# Mega_Shield-v13.net
KiCad netlist of a schematic drawn in EAGLE
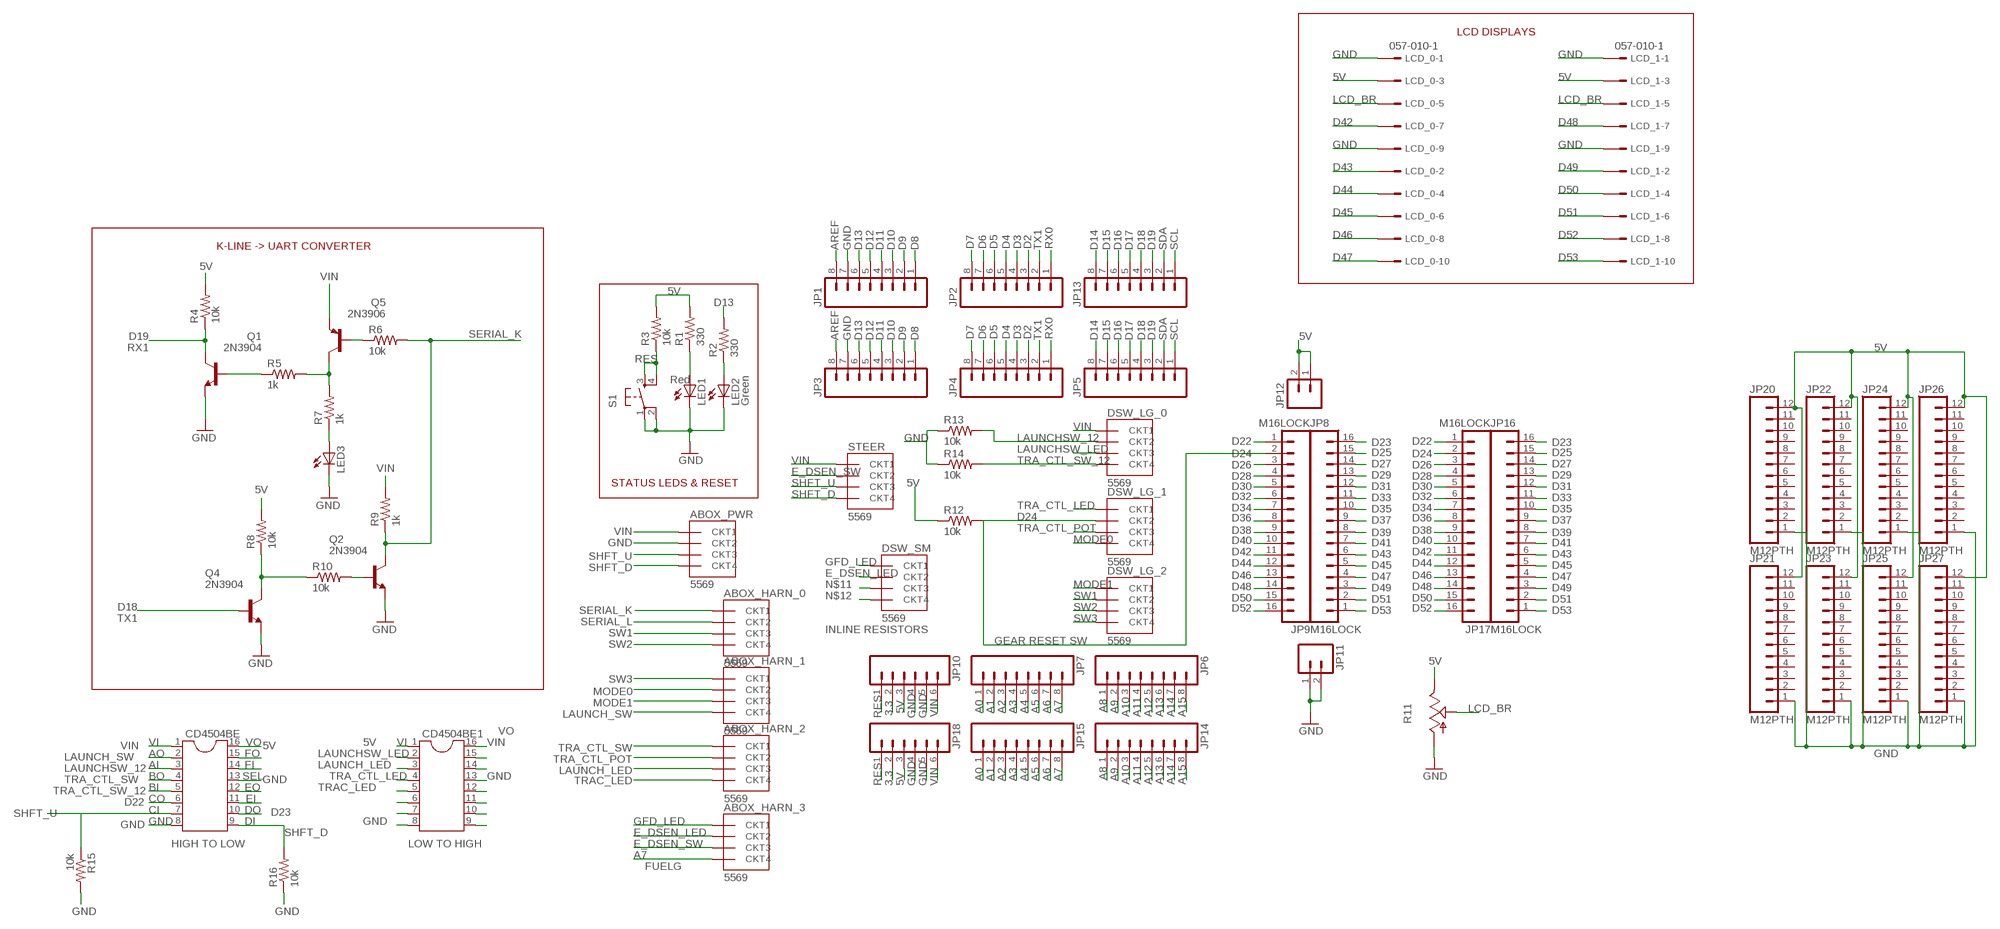
[diagram p0: schematic, sheet 1]

(export (version "E")
  (design (tool "Eeschema 10.0.6"))
  (components
    (comp (ref "ABOX_HARN_0")
      (value "5569")
      (footprint "eagle-import:5569")
      (libsource (lib "eagle-import") (part "5569"))
    )
    (comp (ref "ABOX_HARN_1")
      (value "5569")
      (footprint "eagle-import:5569")
      (libsource (lib "eagle-import") (part "5569"))
    )
    (comp (ref "ABOX_HARN_2")
      (value "5569")
      (footprint "eagle-import:5569")
      (libsource (lib "eagle-import") (part "5569"))
    )
    (comp (ref "ABOX_HARN_3")
      (value "5569")
      (footprint "eagle-import:5569")
      (libsource (lib "eagle-import") (part "5569"))
    )
    (comp (ref "ABOX_PWR")
      (value "5569")
      (footprint "eagle-import:5569")
      (libsource (lib "eagle-import") (part "5569"))
    )
    (comp (ref "CD4504BE")
      (value "DIL16S")
      (footprint "eagle-import:SOCKET-16")
      (libsource (lib "eagle-import") (part "DIL16S"))
    )
    (comp (ref "CD4504BE1")
      (value "DIL16S")
      (footprint "eagle-import:SOCKET-16")
      (libsource (lib "eagle-import") (part "DIL16S"))
    )
    (comp (ref "DSW_LG_0")
      (value "5569")
      (footprint "eagle-import:5569")
      (libsource (lib "eagle-import") (part "5569"))
    )
    (comp (ref "DSW_LG_1")
      (value "5569")
      (footprint "eagle-import:5569")
      (libsource (lib "eagle-import") (part "5569"))
    )
    (comp (ref "DSW_LG_2")
      (value "5569")
      (footprint "eagle-import:5569")
      (libsource (lib "eagle-import") (part "5569"))
    )
    (comp (ref "DSW_SM")
      (value "5569")
      (footprint "eagle-import:5569")
      (libsource (lib "eagle-import") (part "5569"))
    )
    (comp (ref "JP1")
      (value "M08LOCK")
      (footprint "eagle-import:1X08_LOCK")
      (libsource (lib "eagle-import") (part "M08LOCK"))
    )
    (comp (ref "JP2")
      (value "M08LOCK")
      (footprint "eagle-import:1X08_LOCK")
      (libsource (lib "eagle-import") (part "M08LOCK"))
    )
    (comp (ref "JP3")
      (value "M08LOCK")
      (footprint "eagle-import:1X08_LOCK")
      (libsource (lib "eagle-import") (part "M08LOCK"))
    )
    (comp (ref "JP4")
      (value "M08LOCK")
      (footprint "eagle-import:1X08_LOCK")
      (libsource (lib "eagle-import") (part "M08LOCK"))
    )
    (comp (ref "JP5")
      (value "M08LOCK")
      (footprint "eagle-import:1X08_LOCK")
      (libsource (lib "eagle-import") (part "M08LOCK"))
    )
    (comp (ref "JP6")
      (value "M08LOCK")
      (footprint "eagle-import:1X08_LOCK")
      (libsource (lib "eagle-import") (part "M08LOCK"))
    )
    (comp (ref "JP7")
      (value "M08LOCK")
      (footprint "eagle-import:1X08_LOCK")
      (libsource (lib "eagle-import") (part "M08LOCK"))
    )
    (comp (ref "JP8")
      (value "M16LOCK")
      (footprint "eagle-import:1X16_LOCK")
      (libsource (lib "eagle-import") (part "M16LOCK"))
    )
    (comp (ref "JP9")
      (value "M16LOCK")
      (footprint "eagle-import:1X16_LOCK")
      (libsource (lib "eagle-import") (part "M16LOCK"))
    )
    (comp (ref "JP10")
      (value "M06LOCK")
      (footprint "eagle-import:1X06_LOCK")
      (libsource (lib "eagle-import") (part "M06LOCK"))
    )
    (comp (ref "JP11")
      (value "M02LOCK")
      (footprint "eagle-import:1X02_LOCK")
      (libsource (lib "eagle-import") (part "M02LOCK"))
    )
    (comp (ref "JP12")
      (value "M02LOCK")
      (footprint "eagle-import:1X02_LOCK")
      (libsource (lib "eagle-import") (part "M02LOCK"))
    )
    (comp (ref "JP13")
      (value "M08LOCK")
      (footprint "eagle-import:1X08_LOCK")
      (libsource (lib "eagle-import") (part "M08LOCK"))
    )
    (comp (ref "JP14")
      (value "M08LOCK")
      (footprint "eagle-import:1X08_LOCK")
      (libsource (lib "eagle-import") (part "M08LOCK"))
    )
    (comp (ref "JP15")
      (value "M08LOCK")
      (footprint "eagle-import:1X08_LOCK")
      (libsource (lib "eagle-import") (part "M08LOCK"))
    )
    (comp (ref "JP16")
      (value "M16LOCK")
      (footprint "eagle-import:1X16_LOCK")
      (libsource (lib "eagle-import") (part "M16LOCK"))
    )
    (comp (ref "JP17")
      (value "M16LOCK")
      (footprint "eagle-import:1X16_LOCK")
      (libsource (lib "eagle-import") (part "M16LOCK"))
    )
    (comp (ref "JP18")
      (value "M06LOCK")
      (footprint "eagle-import:1X06_LOCK")
      (libsource (lib "eagle-import") (part "M06LOCK"))
    )
    (comp (ref "JP20")
      (value "M12PTH")
      (footprint "eagle-import:1X12")
      (libsource (lib "eagle-import") (part "M12PTH"))
    )
    (comp (ref "JP21")
      (value "M12PTH")
      (footprint "eagle-import:1X12")
      (libsource (lib "eagle-import") (part "M12PTH"))
    )
    (comp (ref "JP22")
      (value "M12PTH")
      (footprint "eagle-import:1X12")
      (libsource (lib "eagle-import") (part "M12PTH"))
    )
    (comp (ref "JP23")
      (value "M12PTH")
      (footprint "eagle-import:1X12")
      (libsource (lib "eagle-import") (part "M12PTH"))
    )
    (comp (ref "JP24")
      (value "M12PTH")
      (footprint "eagle-import:1X12")
      (libsource (lib "eagle-import") (part "M12PTH"))
    )
    (comp (ref "JP25")
      (value "M12PTH")
      (footprint "eagle-import:1X12")
      (libsource (lib "eagle-import") (part "M12PTH"))
    )
    (comp (ref "JP26")
      (value "M12PTH")
      (footprint "eagle-import:1X12")
      (libsource (lib "eagle-import") (part "M12PTH"))
    )
    (comp (ref "JP27")
      (value "M12PTH")
      (footprint "eagle-import:1X12")
      (libsource (lib "eagle-import") (part "M12PTH"))
    )
    (comp (ref "LCD_0")
      (value "057-010-1")
      (footprint "eagle-import:057-010-1")
      (libsource (lib "eagle-import") (part "057-010-1"))
    )
    (comp (ref "LCD_1")
      (value "057-010-1")
      (footprint "eagle-import:057-010-1")
      (libsource (lib "eagle-import") (part "057-010-1"))
    )
    (comp (ref "LED1")
      (value "Red")
      (footprint "eagle-import:LED5MM")
      (libsource (lib "eagle-import") (part "LED5MM"))
    )
    (comp (ref "LED2")
      (value "Green")
      (footprint "eagle-import:LED5MM")
      (libsource (lib "eagle-import") (part "LED5MM"))
    )
    (comp (ref "LED3")
      (value "LED5MM")
      (footprint "eagle-import:LED5MM")
      (libsource (lib "eagle-import") (part "led_LED5MM"))
    )
    (comp (ref "Q1")
      (value "2N3904")
      (footprint "eagle-import:TO92")
      (libsource (lib "eagle-import") (part "2N3904"))
    )
    (comp (ref "Q2")
      (value "2N3904")
      (footprint "eagle-import:TO92")
      (libsource (lib "eagle-import") (part "2N3904"))
    )
    (comp (ref "Q4")
      (value "2N3904")
      (footprint "eagle-import:TO92")
      (libsource (lib "eagle-import") (part "2N3904"))
    )
    (comp (ref "Q5")
      (value "2N3906")
      (footprint "eagle-import:TO92")
      (libsource (lib "eagle-import") (part "2N3906"))
    )
    (comp (ref "R1")
      (value "330")
      (footprint "eagle-import:AXIAL-0.3")
      (libsource (lib "eagle-import") (part "RESISTORPTH1"))
    )
    (comp (ref "R2")
      (value "330")
      (footprint "eagle-import:AXIAL-0.3")
      (libsource (lib "eagle-import") (part "RESISTORPTH1"))
    )
    (comp (ref "R3")
      (value "10k")
      (footprint "eagle-import:AXIAL-0.3")
      (libsource (lib "eagle-import") (part "RESISTORPTH1"))
    )
    (comp (ref "R4")
      (value "10k")
      (footprint "eagle-import:AXIAL-0.3EZ")
      (libsource (lib "eagle-import") (part "RESISTOREZ"))
    )
    (comp (ref "R5")
      (value "1k")
      (footprint "eagle-import:AXIAL-0.3EZ")
      (libsource (lib "eagle-import") (part "RESISTOREZ"))
    )
    (comp (ref "R6")
      (value "10k")
      (footprint "eagle-import:AXIAL-0.3EZ")
      (libsource (lib "eagle-import") (part "RESISTOREZ"))
    )
    (comp (ref "R7")
      (value "1k")
      (footprint "eagle-import:AXIAL-0.3EZ")
      (libsource (lib "eagle-import") (part "RESISTOREZ"))
    )
    (comp (ref "R8")
      (value "10k")
      (footprint "eagle-import:AXIAL-0.3EZ")
      (libsource (lib "eagle-import") (part "RESISTOREZ"))
    )
    (comp (ref "R9")
      (value "1k")
      (footprint "eagle-import:AXIAL-0.3EZ")
      (libsource (lib "eagle-import") (part "RESISTOREZ"))
    )
    (comp (ref "R10")
      (value "10k")
      (footprint "eagle-import:AXIAL-0.3EZ")
      (libsource (lib "eagle-import") (part "RESISTOREZ"))
    )
    (comp (ref "R11")
      (value "TRIM_US-CT6")
      (footprint "eagle-import:CT6")
      (libsource (lib "eagle-import") (part "TRIM_US-CT6"))
    )
    (comp (ref "R12")
      (value "10k")
      (footprint "eagle-import:AXIAL-0.3EZ")
      (libsource (lib "eagle-import") (part "RESISTOREZ"))
    )
    (comp (ref "R13")
      (value "10k")
      (footprint "eagle-import:AXIAL-0.3EZ")
      (libsource (lib "eagle-import") (part "RESISTOREZ"))
    )
    (comp (ref "R14")
      (value "10k")
      (footprint "eagle-import:AXIAL-0.3EZ")
      (libsource (lib "eagle-import") (part "RESISTOREZ"))
    )
    (comp (ref "R15")
      (value "10k")
      (footprint "eagle-import:AXIAL-0.3EZ")
      (libsource (lib "eagle-import") (part "RESISTOREZ"))
    )
    (comp (ref "R16")
      (value "10k")
      (footprint "eagle-import:AXIAL-0.3EZ")
      (libsource (lib "eagle-import") (part "RESISTOREZ"))
    )
    (comp (ref "S1")
      (value "TAC_SWITCHPTH")
      (footprint "eagle-import:TACTILE-PTH")
      (libsource (lib "eagle-import") (part "TAC_SWITCHPTH"))
    )
    (comp (ref "STEER")
      (value "5569")
      (footprint "eagle-import:5569")
      (libsource (lib "eagle-import") (part "5569"))
    )
  )
  (nets
    (net (code "1") (name "/3.3") (class "Default")
      (node (ref "JP10") (pin "2") (pinfunction "2_2") (pintype "passive"))
      (node (ref "JP18") (pin "2") (pinfunction "2_2") (pintype "passive"))
    )
    (net (code "2") (name "/5V") (class "Default")
      (node (ref "CD4504BE") (pin "16") (pinfunction "16_16") (pintype "passive"))
      (node (ref "CD4504BE1") (pin "1") (pinfunction "1_1") (pintype "passive"))
      (node (ref "JP10") (pin "3") (pinfunction "3_3") (pintype "passive"))
      (node (ref "JP12") (pin "1") (pinfunction "1_1") (pintype "passive"))
      (node (ref "JP12") (pin "2") (pinfunction "2_2") (pintype "passive"))
      (node (ref "JP18") (pin "3") (pinfunction "3_3") (pintype "passive"))
      (node (ref "JP20") (pin "12") (pinfunction "12_12") (pintype "passive"))
      (node (ref "JP21") (pin "12") (pinfunction "12_12") (pintype "passive"))
      (node (ref "JP22") (pin "12") (pinfunction "12_12") (pintype "passive"))
      (node (ref "JP23") (pin "12") (pinfunction "12_12") (pintype "passive"))
      (node (ref "JP24") (pin "12") (pinfunction "12_12") (pintype "passive"))
      (node (ref "JP25") (pin "12") (pinfunction "12_12") (pintype "passive"))
      (node (ref "JP26") (pin "12") (pinfunction "12_12") (pintype "passive"))
      (node (ref "JP27") (pin "12") (pinfunction "12_12") (pintype "passive"))
      (node (ref "LCD_0") (pin "3") (pinfunction "S_3") (pintype "passive"))
      (node (ref "LCD_1") (pin "3") (pinfunction "S_3") (pintype "passive"))
      (node (ref "R1") (pin "P$2") (pinfunction "2_P$2") (pintype "passive"))
      (node (ref "R11") (pin "E") (pinfunction "E_E") (pintype "passive"))
      (node (ref "R12") (pin "P$1") (pinfunction "1_P$1") (pintype "passive"))
      (node (ref "R3") (pin "P$2") (pinfunction "2_P$2") (pintype "passive"))
      (node (ref "R4") (pin "P$2") (pinfunction "2_P$2") (pintype "passive"))
      (node (ref "R8") (pin "P$2") (pinfunction "2_P$2") (pintype "passive"))
    )
    (net (code "3") (name "/A0") (class "Default")
      (node (ref "JP15") (pin "1") (pinfunction "1_1") (pintype "passive"))
      (node (ref "JP7") (pin "1") (pinfunction "1_1") (pintype "passive"))
    )
    (net (code "4") (name "/A1") (class "Default")
      (node (ref "JP15") (pin "2") (pinfunction "2_2") (pintype "passive"))
      (node (ref "JP7") (pin "2") (pinfunction "2_2") (pintype "passive"))
    )
    (net (code "5") (name "/A2") (class "Default")
      (node (ref "JP15") (pin "3") (pinfunction "3_3") (pintype "passive"))
      (node (ref "JP7") (pin "3") (pinfunction "3_3") (pintype "passive"))
    )
    (net (code "6") (name "/A3") (class "Default")
      (node (ref "JP15") (pin "4") (pinfunction "4_4") (pintype "passive"))
      (node (ref "JP7") (pin "4") (pinfunction "4_4") (pintype "passive"))
    )
    (net (code "7") (name "/A4") (class "Default")
      (node (ref "JP15") (pin "5") (pinfunction "5_5") (pintype "passive"))
      (node (ref "JP7") (pin "5") (pinfunction "5_5") (pintype "passive"))
    )
    (net (code "8") (name "/A5") (class "Default")
      (node (ref "JP15") (pin "6") (pinfunction "6_6") (pintype "passive"))
      (node (ref "JP7") (pin "6") (pinfunction "6_6") (pintype "passive"))
    )
    (net (code "9") (name "/A6") (class "Default")
      (node (ref "JP15") (pin "7") (pinfunction "7_7") (pintype "passive"))
      (node (ref "JP7") (pin "7") (pinfunction "7_7") (pintype "passive"))
    )
    (net (code "10") (name "/A7") (class "Default")
      (node (ref "ABOX_HARN_3") (pin "CKT4") (pinfunction "CKT4_CKT4") (pintype "bidirectional"))
      (node (ref "JP15") (pin "8") (pinfunction "8_8") (pintype "passive"))
      (node (ref "JP7") (pin "8") (pinfunction "8_8") (pintype "passive"))
    )
    (net (code "11") (name "/A8") (class "Default")
      (node (ref "JP14") (pin "1") (pinfunction "1_1") (pintype "passive"))
      (node (ref "JP6") (pin "1") (pinfunction "1_1") (pintype "passive"))
    )
    (net (code "12") (name "/A9") (class "Default")
      (node (ref "JP14") (pin "2") (pinfunction "2_2") (pintype "passive"))
      (node (ref "JP6") (pin "2") (pinfunction "2_2") (pintype "passive"))
    )
    (net (code "13") (name "/A10") (class "Default")
      (node (ref "JP14") (pin "3") (pinfunction "3_3") (pintype "passive"))
      (node (ref "JP6") (pin "3") (pinfunction "3_3") (pintype "passive"))
    )
    (net (code "14") (name "/A11") (class "Default")
      (node (ref "JP14") (pin "4") (pinfunction "4_4") (pintype "passive"))
      (node (ref "JP6") (pin "4") (pinfunction "4_4") (pintype "passive"))
    )
    (net (code "15") (name "/A12") (class "Default")
      (node (ref "JP14") (pin "5") (pinfunction "5_5") (pintype "passive"))
      (node (ref "JP6") (pin "5") (pinfunction "5_5") (pintype "passive"))
    )
    (net (code "16") (name "/A13") (class "Default")
      (node (ref "JP14") (pin "6") (pinfunction "6_6") (pintype "passive"))
      (node (ref "JP6") (pin "6") (pinfunction "6_6") (pintype "passive"))
    )
    (net (code "17") (name "/A14") (class "Default")
      (node (ref "JP14") (pin "7") (pinfunction "7_7") (pintype "passive"))
      (node (ref "JP6") (pin "7") (pinfunction "7_7") (pintype "passive"))
    )
    (net (code "18") (name "/A15") (class "Default")
      (node (ref "JP14") (pin "8") (pinfunction "8_8") (pintype "passive"))
      (node (ref "JP6") (pin "8") (pinfunction "8_8") (pintype "passive"))
    )
    (net (code "19") (name "/AREF") (class "Default")
      (node (ref "JP1") (pin "8") (pinfunction "8_8") (pintype "passive"))
      (node (ref "JP3") (pin "8") (pinfunction "8_8") (pintype "passive"))
    )
    (net (code "20") (name "/D2") (class "Default")
      (node (ref "JP2") (pin "3") (pinfunction "3_3") (pintype "passive"))
      (node (ref "JP4") (pin "3") (pinfunction "3_3") (pintype "passive"))
    )
    (net (code "21") (name "/D3") (class "Default")
      (node (ref "JP2") (pin "4") (pinfunction "4_4") (pintype "passive"))
      (node (ref "JP4") (pin "4") (pinfunction "4_4") (pintype "passive"))
    )
    (net (code "22") (name "/D4") (class "Default")
      (node (ref "JP2") (pin "5") (pinfunction "5_5") (pintype "passive"))
      (node (ref "JP4") (pin "5") (pinfunction "5_5") (pintype "passive"))
    )
    (net (code "23") (name "/D5") (class "Default")
      (node (ref "JP2") (pin "6") (pinfunction "6_6") (pintype "passive"))
      (node (ref "JP4") (pin "6") (pinfunction "6_6") (pintype "passive"))
    )
    (net (code "24") (name "/D6") (class "Default")
      (node (ref "JP2") (pin "7") (pinfunction "7_7") (pintype "passive"))
      (node (ref "JP4") (pin "7") (pinfunction "7_7") (pintype "passive"))
    )
    (net (code "25") (name "/D7") (class "Default")
      (node (ref "JP2") (pin "8") (pinfunction "8_8") (pintype "passive"))
      (node (ref "JP4") (pin "8") (pinfunction "8_8") (pintype "passive"))
    )
    (net (code "26") (name "/D8") (class "Default")
      (node (ref "JP1") (pin "1") (pinfunction "1_1") (pintype "passive"))
      (node (ref "JP3") (pin "1") (pinfunction "1_1") (pintype "passive"))
    )
    (net (code "27") (name "/D9") (class "Default")
      (node (ref "JP1") (pin "2") (pinfunction "2_2") (pintype "passive"))
      (node (ref "JP3") (pin "2") (pinfunction "2_2") (pintype "passive"))
    )
    (net (code "28") (name "/D10") (class "Default")
      (node (ref "JP1") (pin "3") (pinfunction "3_3") (pintype "passive"))
      (node (ref "JP3") (pin "3") (pinfunction "3_3") (pintype "passive"))
    )
    (net (code "29") (name "/D11") (class "Default")
      (node (ref "JP1") (pin "4") (pinfunction "4_4") (pintype "passive"))
      (node (ref "JP3") (pin "4") (pinfunction "4_4") (pintype "passive"))
    )
    (net (code "30") (name "/D12") (class "Default")
      (node (ref "JP1") (pin "5") (pinfunction "5_5") (pintype "passive"))
      (node (ref "JP3") (pin "5") (pinfunction "5_5") (pintype "passive"))
    )
    (net (code "31") (name "/D13") (class "Default")
      (node (ref "JP1") (pin "6") (pinfunction "6_6") (pintype "passive"))
      (node (ref "JP3") (pin "6") (pinfunction "6_6") (pintype "passive"))
      (node (ref "R2") (pin "P$2") (pinfunction "2_P$2") (pintype "passive"))
    )
    (net (code "32") (name "/D14") (class "Default")
      (node (ref "JP13") (pin "8") (pinfunction "8_8") (pintype "passive"))
      (node (ref "JP5") (pin "8") (pinfunction "8_8") (pintype "passive"))
    )
    (net (code "33") (name "/D15") (class "Default")
      (node (ref "JP13") (pin "7") (pinfunction "7_7") (pintype "passive"))
      (node (ref "JP5") (pin "7") (pinfunction "7_7") (pintype "passive"))
    )
    (net (code "34") (name "/D16") (class "Default")
      (node (ref "JP13") (pin "6") (pinfunction "6_6") (pintype "passive"))
      (node (ref "JP5") (pin "6") (pinfunction "6_6") (pintype "passive"))
    )
    (net (code "35") (name "/D17") (class "Default")
      (node (ref "JP13") (pin "5") (pinfunction "5_5") (pintype "passive"))
      (node (ref "JP5") (pin "5") (pinfunction "5_5") (pintype "passive"))
    )
    (net (code "36") (name "/D18") (class "Default")
      (node (ref "JP13") (pin "4") (pinfunction "4_4") (pintype "passive"))
      (node (ref "JP5") (pin "4") (pinfunction "4_4") (pintype "passive"))
      (node (ref "Q4") (pin "2") (pinfunction "B_2") (pintype "passive"))
    )
    (net (code "37") (name "/D19") (class "Default")
      (node (ref "JP13") (pin "3") (pinfunction "3_3") (pintype "passive"))
      (node (ref "JP5") (pin "3") (pinfunction "3_3") (pintype "passive"))
      (node (ref "Q1") (pin "1") (pinfunction "C_1") (pintype "passive"))
      (node (ref "R4") (pin "P$1") (pinfunction "1_P$1") (pintype "passive"))
    )
    (net (code "38") (name "/D22") (class "Default")
      (node (ref "CD4504BE") (pin "6") (pinfunction "6_6") (pintype "passive"))
      (node (ref "JP17") (pin "1") (pinfunction "1_1") (pintype "passive"))
      (node (ref "JP9") (pin "1") (pinfunction "1_1") (pintype "passive"))
    )
    (net (code "39") (name "/D23") (class "Default")
      (node (ref "CD4504BE") (pin "10") (pinfunction "10_10") (pintype "passive"))
      (node (ref "JP16") (pin "16") (pinfunction "16_16") (pintype "passive"))
      (node (ref "JP8") (pin "16") (pinfunction "16_16") (pintype "passive"))
    )
    (net (code "40") (name "/D24") (class "Default")
      (node (ref "DSW_LG_1") (pin "CKT2") (pinfunction "CKT2_CKT2") (pintype "bidirectional"))
      (node (ref "JP17") (pin "2") (pinfunction "2_2") (pintype "passive"))
      (node (ref "JP9") (pin "2") (pinfunction "2_2") (pintype "passive"))
      (node (ref "R12") (pin "P$2") (pinfunction "2_P$2") (pintype "passive"))
    )
    (net (code "41") (name "/D25") (class "Default")
      (node (ref "JP16") (pin "15") (pinfunction "15_15") (pintype "passive"))
      (node (ref "JP8") (pin "15") (pinfunction "15_15") (pintype "passive"))
    )
    (net (code "42") (name "/D26") (class "Default")
      (node (ref "JP17") (pin "3") (pinfunction "3_3") (pintype "passive"))
      (node (ref "JP9") (pin "3") (pinfunction "3_3") (pintype "passive"))
    )
    (net (code "43") (name "/D27") (class "Default")
      (node (ref "JP16") (pin "14") (pinfunction "14_14") (pintype "passive"))
      (node (ref "JP8") (pin "14") (pinfunction "14_14") (pintype "passive"))
    )
    (net (code "44") (name "/D28") (class "Default")
      (node (ref "JP17") (pin "4") (pinfunction "4_4") (pintype "passive"))
      (node (ref "JP9") (pin "4") (pinfunction "4_4") (pintype "passive"))
    )
    (net (code "45") (name "/D29") (class "Default")
      (node (ref "JP16") (pin "13") (pinfunction "13_13") (pintype "passive"))
      (node (ref "JP8") (pin "13") (pinfunction "13_13") (pintype "passive"))
    )
    (net (code "46") (name "/D30") (class "Default")
      (node (ref "JP17") (pin "5") (pinfunction "5_5") (pintype "passive"))
      (node (ref "JP9") (pin "5") (pinfunction "5_5") (pintype "passive"))
    )
    (net (code "47") (name "/D31") (class "Default")
      (node (ref "JP16") (pin "12") (pinfunction "12_12") (pintype "passive"))
      (node (ref "JP8") (pin "12") (pinfunction "12_12") (pintype "passive"))
    )
    (net (code "48") (name "/D32") (class "Default")
      (node (ref "JP17") (pin "6") (pinfunction "6_6") (pintype "passive"))
      (node (ref "JP9") (pin "6") (pinfunction "6_6") (pintype "passive"))
    )
    (net (code "49") (name "/D33") (class "Default")
      (node (ref "JP16") (pin "11") (pinfunction "11_11") (pintype "passive"))
      (node (ref "JP8") (pin "11") (pinfunction "11_11") (pintype "passive"))
    )
    (net (code "50") (name "/D34") (class "Default")
      (node (ref "JP17") (pin "7") (pinfunction "7_7") (pintype "passive"))
      (node (ref "JP9") (pin "7") (pinfunction "7_7") (pintype "passive"))
    )
    (net (code "51") (name "/D35") (class "Default")
      (node (ref "JP16") (pin "10") (pinfunction "10_10") (pintype "passive"))
      (node (ref "JP8") (pin "10") (pinfunction "10_10") (pintype "passive"))
    )
    (net (code "52") (name "/D36") (class "Default")
      (node (ref "JP17") (pin "8") (pinfunction "8_8") (pintype "passive"))
      (node (ref "JP9") (pin "8") (pinfunction "8_8") (pintype "passive"))
    )
    (net (code "53") (name "/D37") (class "Default")
      (node (ref "JP16") (pin "9") (pinfunction "9_9") (pintype "passive"))
      (node (ref "JP8") (pin "9") (pinfunction "9_9") (pintype "passive"))
    )
    (net (code "54") (name "/D38") (class "Default")
      (node (ref "JP17") (pin "9") (pinfunction "9_9") (pintype "passive"))
      (node (ref "JP9") (pin "9") (pinfunction "9_9") (pintype "passive"))
    )
    (net (code "55") (name "/D39") (class "Default")
      (node (ref "JP16") (pin "8") (pinfunction "8_8") (pintype "passive"))
      (node (ref "JP8") (pin "8") (pinfunction "8_8") (pintype "passive"))
    )
    (net (code "56") (name "/D40") (class "Default")
      (node (ref "JP17") (pin "10") (pinfunction "10_10") (pintype "passive"))
      (node (ref "JP9") (pin "10") (pinfunction "10_10") (pintype "passive"))
    )
    (net (code "57") (name "/D41") (class "Default")
      (node (ref "JP16") (pin "7") (pinfunction "7_7") (pintype "passive"))
      (node (ref "JP8") (pin "7") (pinfunction "7_7") (pintype "passive"))
    )
    (net (code "58") (name "/D42") (class "Default")
      (node (ref "JP17") (pin "11") (pinfunction "11_11") (pintype "passive"))
      (node (ref "JP9") (pin "11") (pinfunction "11_11") (pintype "passive"))
      (node (ref "LCD_0") (pin "7") (pinfunction "S_7") (pintype "passive"))
    )
    (net (code "59") (name "/D43") (class "Default")
      (node (ref "JP16") (pin "6") (pinfunction "6_6") (pintype "passive"))
      (node (ref "JP8") (pin "6") (pinfunction "6_6") (pintype "passive"))
      (node (ref "LCD_0") (pin "2") (pinfunction "S_2") (pintype "passive"))
    )
    (net (code "60") (name "/D44") (class "Default")
      (node (ref "JP17") (pin "12") (pinfunction "12_12") (pintype "passive"))
      (node (ref "JP9") (pin "12") (pinfunction "12_12") (pintype "passive"))
      (node (ref "LCD_0") (pin "4") (pinfunction "S_4") (pintype "passive"))
    )
    (net (code "61") (name "/D45") (class "Default")
      (node (ref "JP16") (pin "5") (pinfunction "5_5") (pintype "passive"))
      (node (ref "JP8") (pin "5") (pinfunction "5_5") (pintype "passive"))
      (node (ref "LCD_0") (pin "6") (pinfunction "S_6") (pintype "passive"))
    )
    (net (code "62") (name "/D46") (class "Default")
      (node (ref "JP17") (pin "13") (pinfunction "13_13") (pintype "passive"))
      (node (ref "JP9") (pin "13") (pinfunction "13_13") (pintype "passive"))
      (node (ref "LCD_0") (pin "8") (pinfunction "S_8") (pintype "passive"))
    )
    (net (code "63") (name "/D47") (class "Default")
      (node (ref "JP16") (pin "4") (pinfunction "4_4") (pintype "passive"))
      (node (ref "JP8") (pin "4") (pinfunction "4_4") (pintype "passive"))
      (node (ref "LCD_0") (pin "10") (pinfunction "S_10") (pintype "passive"))
    )
    (net (code "64") (name "/D48") (class "Default")
      (node (ref "JP17") (pin "14") (pinfunction "14_14") (pintype "passive"))
      (node (ref "JP9") (pin "14") (pinfunction "14_14") (pintype "passive"))
      (node (ref "LCD_1") (pin "7") (pinfunction "S_7") (pintype "passive"))
    )
    (net (code "65") (name "/D49") (class "Default")
      (node (ref "JP16") (pin "3") (pinfunction "3_3") (pintype "passive"))
      (node (ref "JP8") (pin "3") (pinfunction "3_3") (pintype "passive"))
      (node (ref "LCD_1") (pin "2") (pinfunction "S_2") (pintype "passive"))
    )
    (net (code "66") (name "/D50") (class "Default")
      (node (ref "JP17") (pin "15") (pinfunction "15_15") (pintype "passive"))
      (node (ref "JP9") (pin "15") (pinfunction "15_15") (pintype "passive"))
      (node (ref "LCD_1") (pin "4") (pinfunction "S_4") (pintype "passive"))
    )
    (net (code "67") (name "/D51") (class "Default")
      (node (ref "JP16") (pin "2") (pinfunction "2_2") (pintype "passive"))
      (node (ref "JP8") (pin "2") (pinfunction "2_2") (pintype "passive"))
      (node (ref "LCD_1") (pin "6") (pinfunction "S_6") (pintype "passive"))
    )
    (net (code "68") (name "/D52") (class "Default")
      (node (ref "JP17") (pin "16") (pinfunction "16_16") (pintype "passive"))
      (node (ref "JP9") (pin "16") (pinfunction "16_16") (pintype "passive"))
      (node (ref "LCD_1") (pin "8") (pinfunction "S_8") (pintype "passive"))
    )
    (net (code "69") (name "/D53") (class "Default")
      (node (ref "JP16") (pin "1") (pinfunction "1_1") (pintype "passive"))
      (node (ref "JP8") (pin "1") (pinfunction "1_1") (pintype "passive"))
      (node (ref "LCD_1") (pin "10") (pinfunction "S_10") (pintype "passive"))
    )
    (net (code "70") (name "/E_DSEN_LED") (class "Default")
      (node (ref "ABOX_HARN_3") (pin "CKT2") (pinfunction "CKT2_CKT2") (pintype "bidirectional"))
      (node (ref "DSW_SM") (pin "CKT2") (pinfunction "CKT2_CKT2") (pintype "bidirectional"))
    )
    (net (code "71") (name "/E_DSEN_SW") (class "Default")
      (node (ref "ABOX_HARN_3") (pin "CKT3") (pinfunction "CKT3_CKT3") (pintype "bidirectional"))
      (node (ref "STEER") (pin "CKT2") (pinfunction "CKT2_CKT2") (pintype "bidirectional"))
    )
    (net (code "72") (name "/GFD_LED") (class "Default")
      (node (ref "ABOX_HARN_3") (pin "CKT1") (pinfunction "CKT1_CKT1") (pintype "bidirectional"))
      (node (ref "DSW_SM") (pin "CKT1") (pinfunction "CKT1_CKT1") (pintype "bidirectional"))
    )
    (net (code "73") (name "/LAUNCHSW_12") (class "Default")
      (node (ref "CD4504BE") (pin "3") (pinfunction "3_3") (pintype "passive"))
      (node (ref "DSW_LG_0") (pin "CKT2") (pinfunction "CKT2_CKT2") (pintype "bidirectional"))
      (node (ref "R13") (pin "P$2") (pinfunction "2_P$2") (pintype "passive"))
    )
    (net (code "74") (name "/LAUNCHSW_LED") (class "Default")
      (node (ref "CD4504BE1") (pin "2") (pinfunction "2_2") (pintype "passive"))
      (node (ref "DSW_LG_0") (pin "CKT3") (pinfunction "CKT3_CKT3") (pintype "bidirectional"))
    )
    (net (code "75") (name "/LAUNCH_LED") (class "Default")
      (node (ref "ABOX_HARN_2") (pin "CKT3") (pinfunction "CKT3_CKT3") (pintype "bidirectional"))
      (node (ref "CD4504BE1") (pin "3") (pinfunction "3_3") (pintype "passive"))
    )
    (net (code "76") (name "/LAUNCH_SW") (class "Default")
      (node (ref "ABOX_HARN_1") (pin "CKT4") (pinfunction "CKT4_CKT4") (pintype "bidirectional"))
      (node (ref "CD4504BE") (pin "2") (pinfunction "2_2") (pintype "passive"))
    )
    (net (code "77") (name "/LCD_BR") (class "Default")
      (node (ref "LCD_0") (pin "5") (pinfunction "S_5") (pintype "passive"))
      (node (ref "LCD_1") (pin "5") (pinfunction "S_5") (pintype "passive"))
      (node (ref "R11") (pin "S") (pinfunction "S_S") (pintype "passive"))
    )
    (net (code "78") (name "/MODE0") (class "Default")
      (node (ref "ABOX_HARN_1") (pin "CKT2") (pinfunction "CKT2_CKT2") (pintype "bidirectional"))
      (node (ref "DSW_LG_1") (pin "CKT4") (pinfunction "CKT4_CKT4") (pintype "bidirectional"))
    )
    (net (code "79") (name "/MODE1") (class "Default")
      (node (ref "ABOX_HARN_1") (pin "CKT3") (pinfunction "CKT3_CKT3") (pintype "bidirectional"))
      (node (ref "DSW_LG_2") (pin "CKT1") (pinfunction "CKT1_CKT1") (pintype "bidirectional"))
    )
    (net (code "80") (name "/N$11") (class "Default")
      (node (ref "DSW_SM") (pin "CKT3") (pinfunction "CKT3_CKT3") (pintype "bidirectional"))
    )
    (net (code "81") (name "/N$12") (class "Default")
      (node (ref "DSW_SM") (pin "CKT4") (pinfunction "CKT4_CKT4") (pintype "bidirectional"))
    )
    (net (code "82") (name "/RES") (class "Default")
      (node (ref "JP10") (pin "1") (pinfunction "1_1") (pintype "passive"))
      (node (ref "JP18") (pin "1") (pinfunction "1_1") (pintype "passive"))
      (node (ref "R3") (pin "P$1") (pinfunction "1_P$1") (pintype "passive"))
      (node (ref "S1") (pin "3") (pinfunction "3_3") (pintype "passive"))
      (node (ref "S1") (pin "4") (pinfunction "4_4") (pintype "passive"))
    )
    (net (code "83") (name "/RX0") (class "Default")
      (node (ref "JP2") (pin "1") (pinfunction "1_1") (pintype "passive"))
      (node (ref "JP4") (pin "1") (pinfunction "1_1") (pintype "passive"))
    )
    (net (code "84") (name "/SCL") (class "Default")
      (node (ref "JP13") (pin "1") (pinfunction "1_1") (pintype "passive"))
      (node (ref "JP5") (pin "1") (pinfunction "1_1") (pintype "passive"))
    )
    (net (code "85") (name "/SDA") (class "Default")
      (node (ref "JP13") (pin "2") (pinfunction "2_2") (pintype "passive"))
      (node (ref "JP5") (pin "2") (pinfunction "2_2") (pintype "passive"))
    )
    (net (code "86") (name "/SERIAL_K") (class "Default")
      (node (ref "ABOX_HARN_0") (pin "CKT1") (pinfunction "CKT1_CKT1") (pintype "bidirectional"))
      (node (ref "Q2") (pin "1") (pinfunction "C_1") (pintype "passive"))
      (node (ref "R6") (pin "P$2") (pinfunction "2_P$2") (pintype "passive"))
      (node (ref "R9") (pin "P$1") (pinfunction "1_P$1") (pintype "passive"))
    )
    (net (code "87") (name "/SERIAL_L") (class "Default")
      (node (ref "ABOX_HARN_0") (pin "CKT2") (pinfunction "CKT2_CKT2") (pintype "bidirectional"))
    )
    (net (code "88") (name "/SHFT_D") (class "Default")
      (node (ref "ABOX_PWR") (pin "CKT4") (pinfunction "CKT4_CKT4") (pintype "bidirectional"))
      (node (ref "CD4504BE") (pin "9") (pinfunction "9_9") (pintype "passive"))
      (node (ref "R16") (pin "P$2") (pinfunction "2_P$2") (pintype "passive"))
      (node (ref "STEER") (pin "CKT4") (pinfunction "CKT4_CKT4") (pintype "bidirectional"))
    )
    (net (code "89") (name "/SHFT_U") (class "Default")
      (node (ref "ABOX_PWR") (pin "CKT3") (pinfunction "CKT3_CKT3") (pintype "bidirectional"))
      (node (ref "CD4504BE") (pin "7") (pinfunction "7_7") (pintype "passive"))
      (node (ref "R15") (pin "P$1") (pinfunction "1_P$1") (pintype "passive"))
      (node (ref "STEER") (pin "CKT3") (pinfunction "CKT3_CKT3") (pintype "bidirectional"))
    )
    (net (code "90") (name "/SW1") (class "Default")
      (node (ref "ABOX_HARN_0") (pin "CKT3") (pinfunction "CKT3_CKT3") (pintype "bidirectional"))
      (node (ref "DSW_LG_2") (pin "CKT2") (pinfunction "CKT2_CKT2") (pintype "bidirectional"))
    )
    (net (code "91") (name "/SW2") (class "Default")
      (node (ref "ABOX_HARN_0") (pin "CKT4") (pinfunction "CKT4_CKT4") (pintype "bidirectional"))
      (node (ref "DSW_LG_2") (pin "CKT3") (pinfunction "CKT3_CKT3") (pintype "bidirectional"))
    )
    (net (code "92") (name "/SW3") (class "Default")
      (node (ref "ABOX_HARN_1") (pin "CKT1") (pinfunction "CKT1_CKT1") (pintype "bidirectional"))
      (node (ref "DSW_LG_2") (pin "CKT4") (pinfunction "CKT4_CKT4") (pintype "bidirectional"))
    )
    (net (code "93") (name "/TRAC_LED") (class "Default")
      (node (ref "ABOX_HARN_2") (pin "CKT4") (pinfunction "CKT4_CKT4") (pintype "bidirectional"))
      (node (ref "CD4504BE1") (pin "5") (pinfunction "5_5") (pintype "passive"))
    )
    (net (code "94") (name "/TRA_CTL_LED") (class "Default")
      (node (ref "CD4504BE1") (pin "4") (pinfunction "4_4") (pintype "passive"))
      (node (ref "DSW_LG_1") (pin "CKT1") (pinfunction "CKT1_CKT1") (pintype "bidirectional"))
    )
    (net (code "95") (name "/TRA_CTL_POT") (class "Default")
      (node (ref "ABOX_HARN_2") (pin "CKT2") (pinfunction "CKT2_CKT2") (pintype "bidirectional"))
      (node (ref "DSW_LG_1") (pin "CKT3") (pinfunction "CKT3_CKT3") (pintype "bidirectional"))
    )
    (net (code "96") (name "/TRA_CTL_SW") (class "Default")
      (node (ref "ABOX_HARN_2") (pin "CKT1") (pinfunction "CKT1_CKT1") (pintype "bidirectional"))
      (node (ref "CD4504BE") (pin "4") (pinfunction "4_4") (pintype "passive"))
    )
    (net (code "97") (name "/TRA_CTL_SW_12") (class "Default")
      (node (ref "CD4504BE") (pin "5") (pinfunction "5_5") (pintype "passive"))
      (node (ref "DSW_LG_0") (pin "CKT4") (pinfunction "CKT4_CKT4") (pintype "bidirectional"))
      (node (ref "R14") (pin "P$2") (pinfunction "2_P$2") (pintype "passive"))
    )
    (net (code "98") (name "/TX1") (class "Default")
      (node (ref "JP2") (pin "2") (pinfunction "2_2") (pintype "passive"))
      (node (ref "JP4") (pin "2") (pinfunction "2_2") (pintype "passive"))
    )
    (net (code "99") (name "/VIN") (class "Default")
      (node (ref "ABOX_PWR") (pin "CKT1") (pinfunction "CKT1_CKT1") (pintype "bidirectional"))
      (node (ref "CD4504BE") (pin "1") (pinfunction "1_1") (pintype "passive"))
      (node (ref "CD4504BE1") (pin "16") (pinfunction "16_16") (pintype "passive"))
      (node (ref "DSW_LG_0") (pin "CKT1") (pinfunction "CKT1_CKT1") (pintype "bidirectional"))
      (node (ref "JP10") (pin "6") (pinfunction "6_6") (pintype "passive"))
      (node (ref "JP18") (pin "6") (pinfunction "6_6") (pintype "passive"))
      (node (ref "Q5") (pin "3") (pinfunction "E_3") (pintype "passive"))
      (node (ref "R9") (pin "P$2") (pinfunction "2_P$2") (pintype "passive"))
      (node (ref "STEER") (pin "CKT1") (pinfunction "CKT1_CKT1") (pintype "bidirectional"))
    )
    (net (code "100") (name "GND") (class "Default")
      (node (ref "ABOX_PWR") (pin "CKT2") (pinfunction "CKT2_CKT2") (pintype "bidirectional"))
      (node (ref "CD4504BE") (pin "13") (pinfunction "13_13") (pintype "passive"))
      (node (ref "CD4504BE") (pin "8") (pinfunction "8_8") (pintype "passive"))
      (node (ref "CD4504BE1") (pin "13") (pinfunction "13_13") (pintype "passive"))
      (node (ref "CD4504BE1") (pin "8") (pinfunction "8_8") (pintype "passive"))
      (node (ref "JP1") (pin "7") (pinfunction "7_7") (pintype "passive"))
      (node (ref "JP10") (pin "4") (pinfunction "4_4") (pintype "passive"))
      (node (ref "JP10") (pin "5") (pinfunction "5_5") (pintype "passive"))
      (node (ref "JP11") (pin "1") (pinfunction "1_1") (pintype "passive"))
      (node (ref "JP11") (pin "2") (pinfunction "2_2") (pintype "passive"))
      (node (ref "JP18") (pin "4") (pinfunction "4_4") (pintype "passive"))
      (node (ref "JP18") (pin "5") (pinfunction "5_5") (pintype "passive"))
      (node (ref "JP20") (pin "1") (pinfunction "1_1") (pintype "passive"))
      (node (ref "JP21") (pin "1") (pinfunction "1_1") (pintype "passive"))
      (node (ref "JP22") (pin "1") (pinfunction "1_1") (pintype "passive"))
      (node (ref "JP23") (pin "1") (pinfunction "1_1") (pintype "passive"))
      (node (ref "JP24") (pin "1") (pinfunction "1_1") (pintype "passive"))
      (node (ref "JP25") (pin "1") (pinfunction "1_1") (pintype "passive"))
      (node (ref "JP26") (pin "1") (pinfunction "1_1") (pintype "passive"))
      (node (ref "JP27") (pin "1") (pinfunction "1_1") (pintype "passive"))
      (node (ref "JP3") (pin "7") (pinfunction "7_7") (pintype "passive"))
      (node (ref "LCD_0") (pin "1") (pinfunction "S_1") (pintype "passive"))
      (node (ref "LCD_0") (pin "9") (pinfunction "S_9") (pintype "passive"))
      (node (ref "LCD_1") (pin "1") (pinfunction "S_1") (pintype "passive"))
      (node (ref "LCD_1") (pin "9") (pinfunction "S_9") (pintype "passive"))
      (node (ref "LED1") (pin "K") (pinfunction "C_K") (pintype "passive"))
      (node (ref "LED2") (pin "K") (pinfunction "C_K") (pintype "passive"))
      (node (ref "LED3") (pin "K") (pinfunction "C_K") (pintype "passive"))
      (node (ref "Q1") (pin "3") (pinfunction "E_3") (pintype "passive"))
      (node (ref "Q2") (pin "3") (pinfunction "E_3") (pintype "passive"))
      (node (ref "Q4") (pin "3") (pinfunction "E_3") (pintype "passive"))
      (node (ref "R11") (pin "A") (pinfunction "A_A") (pintype "passive"))
      (node (ref "R13") (pin "P$1") (pinfunction "1_P$1") (pintype "passive"))
      (node (ref "R14") (pin "P$1") (pinfunction "1_P$1") (pintype "passive"))
      (node (ref "R15") (pin "P$2") (pinfunction "2_P$2") (pintype "passive"))
      (node (ref "R16") (pin "P$1") (pinfunction "1_P$1") (pintype "passive"))
      (node (ref "S1") (pin "1") (pinfunction "1_1") (pintype "passive"))
      (node (ref "S1") (pin "2") (pinfunction "2_2") (pintype "passive"))
    )
    (net (code "101") (name "Net-(Q1-B)") (class "Default")
      (node (ref "Q1") (pin "2") (pinfunction "B_2") (pintype "passive"))
      (node (ref "R5") (pin "P$1") (pinfunction "1_P$1") (pintype "passive"))
    )
    (net (code "102") (name "Net-(Q2-B)") (class "Default")
      (node (ref "Q2") (pin "2") (pinfunction "B_2") (pintype "passive"))
      (node (ref "R10") (pin "P$2") (pinfunction "2_P$2") (pintype "passive"))
    )
    (net (code "103") (name "Net-(Q4-C)") (class "Default")
      (node (ref "Q4") (pin "1") (pinfunction "C_1") (pintype "passive"))
      (node (ref "R10") (pin "P$1") (pinfunction "1_P$1") (pintype "passive"))
      (node (ref "R8") (pin "P$1") (pinfunction "1_P$1") (pintype "passive"))
    )
    (net (code "104") (name "Net-(Q5-B)") (class "Default")
      (node (ref "Q5") (pin "2") (pinfunction "B_2") (pintype "passive"))
      (node (ref "R6") (pin "P$1") (pinfunction "1_P$1") (pintype "passive"))
    )
    (net (code "105") (name "Net-(Q5-C)") (class "Default")
      (node (ref "Q5") (pin "1") (pinfunction "C_1") (pintype "passive"))
      (node (ref "R5") (pin "P$2") (pinfunction "2_P$2") (pintype "passive"))
      (node (ref "R7") (pin "P$2") (pinfunction "2_P$2") (pintype "passive"))
    )
    (net (code "106") (name "Net-(R1-1)") (class "Default")
      (node (ref "LED1") (pin "A") (pinfunction "A_A") (pintype "passive"))
      (node (ref "R1") (pin "P$1") (pinfunction "1_P$1") (pintype "passive"))
    )
    (net (code "107") (name "Net-(R2-1)") (class "Default")
      (node (ref "LED2") (pin "A") (pinfunction "A_A") (pintype "passive"))
      (node (ref "R2") (pin "P$1") (pinfunction "1_P$1") (pintype "passive"))
    )
    (net (code "108") (name "Net-(R7-1)") (class "Default")
      (node (ref "LED3") (pin "A") (pinfunction "A_A") (pintype "passive"))
      (node (ref "R7") (pin "P$1") (pinfunction "1_P$1") (pintype "passive"))
    )
    (net (code "109") (name "unconnected-(CD4504BE-Pad11)") (class "Default")
      (node (ref "CD4504BE") (pin "11") (pinfunction "11_11") (pintype "passive"))
    )
    (net (code "110") (name "unconnected-(CD4504BE-Pad12)") (class "Default")
      (node (ref "CD4504BE") (pin "12") (pinfunction "12_12") (pintype "passive"))
    )
    (net (code "111") (name "unconnected-(CD4504BE-Pad14)") (class "Default")
      (node (ref "CD4504BE") (pin "14") (pinfunction "14_14") (pintype "passive"))
    )
    (net (code "112") (name "unconnected-(CD4504BE-Pad15)") (class "Default")
      (node (ref "CD4504BE") (pin "15") (pinfunction "15_15") (pintype "passive"))
    )
    (net (code "113") (name "unconnected-(CD4504BE1-Pad6)") (class "Default")
      (node (ref "CD4504BE1") (pin "6") (pinfunction "6_6") (pintype "passive"))
    )
    (net (code "114") (name "unconnected-(CD4504BE1-Pad7)") (class "Default")
      (node (ref "CD4504BE1") (pin "7") (pinfunction "7_7") (pintype "passive"))
    )
    (net (code "115") (name "unconnected-(CD4504BE1-Pad9)") (class "Default")
      (node (ref "CD4504BE1") (pin "9") (pinfunction "9_9") (pintype "passive"))
    )
    (net (code "116") (name "unconnected-(CD4504BE1-Pad10)") (class "Default")
      (node (ref "CD4504BE1") (pin "10") (pinfunction "10_10") (pintype "passive"))
    )
    (net (code "117") (name "unconnected-(CD4504BE1-Pad11)") (class "Default")
      (node (ref "CD4504BE1") (pin "11") (pinfunction "11_11") (pintype "passive"))
    )
    (net (code "118") (name "unconnected-(CD4504BE1-Pad12)") (class "Default")
      (node (ref "CD4504BE1") (pin "12") (pinfunction "12_12") (pintype "passive"))
    )
    (net (code "119") (name "unconnected-(CD4504BE1-Pad14)") (class "Default")
      (node (ref "CD4504BE1") (pin "14") (pinfunction "14_14") (pintype "passive"))
    )
    (net (code "120") (name "unconnected-(CD4504BE1-Pad15)") (class "Default")
      (node (ref "CD4504BE1") (pin "15") (pinfunction "15_15") (pintype "passive"))
    )
    (net (code "121") (name "unconnected-(JP20-Pad2)") (class "Default")
      (node (ref "JP20") (pin "2") (pinfunction "2_2") (pintype "passive"))
    )
    (net (code "122") (name "unconnected-(JP20-Pad3)") (class "Default")
      (node (ref "JP20") (pin "3") (pinfunction "3_3") (pintype "passive"))
    )
    (net (code "123") (name "unconnected-(JP20-Pad4)") (class "Default")
      (node (ref "JP20") (pin "4") (pinfunction "4_4") (pintype "passive"))
    )
    (net (code "124") (name "unconnected-(JP20-Pad5)") (class "Default")
      (node (ref "JP20") (pin "5") (pinfunction "5_5") (pintype "passive"))
    )
    (net (code "125") (name "unconnected-(JP20-Pad6)") (class "Default")
      (node (ref "JP20") (pin "6") (pinfunction "6_6") (pintype "passive"))
    )
    (net (code "126") (name "unconnected-(JP20-Pad7)") (class "Default")
      (node (ref "JP20") (pin "7") (pinfunction "7_7") (pintype "passive"))
    )
    (net (code "127") (name "unconnected-(JP20-Pad8)") (class "Default")
      (node (ref "JP20") (pin "8") (pinfunction "8_8") (pintype "passive"))
    )
    (net (code "128") (name "unconnected-(JP20-Pad9)") (class "Default")
      (node (ref "JP20") (pin "9") (pinfunction "9_9") (pintype "passive"))
    )
    (net (code "129") (name "unconnected-(JP20-Pad10)") (class "Default")
      (node (ref "JP20") (pin "10") (pinfunction "10_10") (pintype "passive"))
    )
    (net (code "130") (name "unconnected-(JP20-Pad11)") (class "Default")
      (node (ref "JP20") (pin "11") (pinfunction "11_11") (pintype "passive"))
    )
    (net (code "131") (name "unconnected-(JP21-Pad2)") (class "Default")
      (node (ref "JP21") (pin "2") (pinfunction "2_2") (pintype "passive"))
    )
    (net (code "132") (name "unconnected-(JP21-Pad3)") (class "Default")
      (node (ref "JP21") (pin "3") (pinfunction "3_3") (pintype "passive"))
    )
    (net (code "133") (name "unconnected-(JP21-Pad4)") (class "Default")
      (node (ref "JP21") (pin "4") (pinfunction "4_4") (pintype "passive"))
    )
    (net (code "134") (name "unconnected-(JP21-Pad5)") (class "Default")
      (node (ref "JP21") (pin "5") (pinfunction "5_5") (pintype "passive"))
    )
    (net (code "135") (name "unconnected-(JP21-Pad6)") (class "Default")
      (node (ref "JP21") (pin "6") (pinfunction "6_6") (pintype "passive"))
    )
    (net (code "136") (name "unconnected-(JP21-Pad7)") (class "Default")
      (node (ref "JP21") (pin "7") (pinfunction "7_7") (pintype "passive"))
    )
    (net (code "137") (name "unconnected-(JP21-Pad8)") (class "Default")
      (node (ref "JP21") (pin "8") (pinfunction "8_8") (pintype "passive"))
    )
    (net (code "138") (name "unconnected-(JP21-Pad9)") (class "Default")
      (node (ref "JP21") (pin "9") (pinfunction "9_9") (pintype "passive"))
    )
    (net (code "139") (name "unconnected-(JP21-Pad10)") (class "Default")
      (node (ref "JP21") (pin "10") (pinfunction "10_10") (pintype "passive"))
    )
    (net (code "140") (name "unconnected-(JP21-Pad11)") (class "Default")
      (node (ref "JP21") (pin "11") (pinfunction "11_11") (pintype "passive"))
    )
    (net (code "141") (name "unconnected-(JP22-Pad2)") (class "Default")
      (node (ref "JP22") (pin "2") (pinfunction "2_2") (pintype "passive"))
    )
    (net (code "142") (name "unconnected-(JP22-Pad3)") (class "Default")
      (node (ref "JP22") (pin "3") (pinfunction "3_3") (pintype "passive"))
    )
    (net (code "143") (name "unconnected-(JP22-Pad4)") (class "Default")
      (node (ref "JP22") (pin "4") (pinfunction "4_4") (pintype "passive"))
    )
    (net (code "144") (name "unconnected-(JP22-Pad5)") (class "Default")
      (node (ref "JP22") (pin "5") (pinfunction "5_5") (pintype "passive"))
    )
    (net (code "145") (name "unconnected-(JP22-Pad6)") (class "Default")
      (node (ref "JP22") (pin "6") (pinfunction "6_6") (pintype "passive"))
    )
    (net (code "146") (name "unconnected-(JP22-Pad7)") (class "Default")
      (node (ref "JP22") (pin "7") (pinfunction "7_7") (pintype "passive"))
    )
    (net (code "147") (name "unconnected-(JP22-Pad8)") (class "Default")
      (node (ref "JP22") (pin "8") (pinfunction "8_8") (pintype "passive"))
    )
    (net (code "148") (name "unconnected-(JP22-Pad9)") (class "Default")
      (node (ref "JP22") (pin "9") (pinfunction "9_9") (pintype "passive"))
    )
    (net (code "149") (name "unconnected-(JP22-Pad10)") (class "Default")
      (node (ref "JP22") (pin "10") (pinfunction "10_10") (pintype "passive"))
    )
    (net (code "150") (name "unconnected-(JP22-Pad11)") (class "Default")
      (node (ref "JP22") (pin "11") (pinfunction "11_11") (pintype "passive"))
    )
    (net (code "151") (name "unconnected-(JP23-Pad2)") (class "Default")
      (node (ref "JP23") (pin "2") (pinfunction "2_2") (pintype "passive"))
    )
    (net (code "152") (name "unconnected-(JP23-Pad3)") (class "Default")
      (node (ref "JP23") (pin "3") (pinfunction "3_3") (pintype "passive"))
    )
    (net (code "153") (name "unconnected-(JP23-Pad4)") (class "Default")
      (node (ref "JP23") (pin "4") (pinfunction "4_4") (pintype "passive"))
    )
    (net (code "154") (name "unconnected-(JP23-Pad5)") (class "Default")
      (node (ref "JP23") (pin "5") (pinfunction "5_5") (pintype "passive"))
    )
    (net (code "155") (name "unconnected-(JP23-Pad6)") (class "Default")
      (node (ref "JP23") (pin "6") (pinfunction "6_6") (pintype "passive"))
    )
    (net (code "156") (name "unconnected-(JP23-Pad7)") (class "Default")
      (node (ref "JP23") (pin "7") (pinfunction "7_7") (pintype "passive"))
    )
    (net (code "157") (name "unconnected-(JP23-Pad8)") (class "Default")
      (node (ref "JP23") (pin "8") (pinfunction "8_8") (pintype "passive"))
    )
    (net (code "158") (name "unconnected-(JP23-Pad9)") (class "Default")
      (node (ref "JP23") (pin "9") (pinfunction "9_9") (pintype "passive"))
    )
    (net (code "159") (name "unconnected-(JP23-Pad10)") (class "Default")
      (node (ref "JP23") (pin "10") (pinfunction "10_10") (pintype "passive"))
    )
    (net (code "160") (name "unconnected-(JP23-Pad11)") (class "Default")
      (node (ref "JP23") (pin "11") (pinfunction "11_11") (pintype "passive"))
    )
    (net (code "161") (name "unconnected-(JP24-Pad2)") (class "Default")
      (node (ref "JP24") (pin "2") (pinfunction "2_2") (pintype "passive"))
    )
    (net (code "162") (name "unconnected-(JP24-Pad3)") (class "Default")
      (node (ref "JP24") (pin "3") (pinfunction "3_3") (pintype "passive"))
    )
    (net (code "163") (name "unconnected-(JP24-Pad4)") (class "Default")
      (node (ref "JP24") (pin "4") (pinfunction "4_4") (pintype "passive"))
    )
    (net (code "164") (name "unconnected-(JP24-Pad5)") (class "Default")
      (node (ref "JP24") (pin "5") (pinfunction "5_5") (pintype "passive"))
    )
    (net (code "165") (name "unconnected-(JP24-Pad6)") (class "Default")
      (node (ref "JP24") (pin "6") (pinfunction "6_6") (pintype "passive"))
    )
    (net (code "166") (name "unconnected-(JP24-Pad7)") (class "Default")
      (node (ref "JP24") (pin "7") (pinfunction "7_7") (pintype "passive"))
    )
    (net (code "167") (name "unconnected-(JP24-Pad8)") (class "Default")
      (node (ref "JP24") (pin "8") (pinfunction "8_8") (pintype "passive"))
    )
    (net (code "168") (name "unconnected-(JP24-Pad9)") (class "Default")
      (node (ref "JP24") (pin "9") (pinfunction "9_9") (pintype "passive"))
    )
    (net (code "169") (name "unconnected-(JP24-Pad10)") (class "Default")
      (node (ref "JP24") (pin "10") (pinfunction "10_10") (pintype "passive"))
    )
    (net (code "170") (name "unconnected-(JP24-Pad11)") (class "Default")
      (node (ref "JP24") (pin "11") (pinfunction "11_11") (pintype "passive"))
    )
    (net (code "171") (name "unconnected-(JP25-Pad2)") (class "Default")
      (node (ref "JP25") (pin "2") (pinfunction "2_2") (pintype "passive"))
    )
    (net (code "172") (name "unconnected-(JP25-Pad3)") (class "Default")
      (node (ref "JP25") (pin "3") (pinfunction "3_3") (pintype "passive"))
    )
    (net (code "173") (name "unconnected-(JP25-Pad4)") (class "Default")
      (node (ref "JP25") (pin "4") (pinfunction "4_4") (pintype "passive"))
    )
    (net (code "174") (name "unconnected-(JP25-Pad5)") (class "Default")
      (node (ref "JP25") (pin "5") (pinfunction "5_5") (pintype "passive"))
    )
    (net (code "175") (name "unconnected-(JP25-Pad6)") (class "Default")
      (node (ref "JP25") (pin "6") (pinfunction "6_6") (pintype "passive"))
    )
    (net (code "176") (name "unconnected-(JP25-Pad7)") (class "Default")
      (node (ref "JP25") (pin "7") (pinfunction "7_7") (pintype "passive"))
    )
    (net (code "177") (name "unconnected-(JP25-Pad8)") (class "Default")
      (node (ref "JP25") (pin "8") (pinfunction "8_8") (pintype "passive"))
    )
    (net (code "178") (name "unconnected-(JP25-Pad9)") (class "Default")
      (node (ref "JP25") (pin "9") (pinfunction "9_9") (pintype "passive"))
    )
    (net (code "179") (name "unconnected-(JP25-Pad10)") (class "Default")
      (node (ref "JP25") (pin "10") (pinfunction "10_10") (pintype "passive"))
    )
    (net (code "180") (name "unconnected-(JP25-Pad11)") (class "Default")
      (node (ref "JP25") (pin "11") (pinfunction "11_11") (pintype "passive"))
    )
    (net (code "181") (name "unconnected-(JP26-Pad2)") (class "Default")
      (node (ref "JP26") (pin "2") (pinfunction "2_2") (pintype "passive"))
    )
    (net (code "182") (name "unconnected-(JP26-Pad3)") (class "Default")
      (node (ref "JP26") (pin "3") (pinfunction "3_3") (pintype "passive"))
    )
    (net (code "183") (name "unconnected-(JP26-Pad4)") (class "Default")
      (node (ref "JP26") (pin "4") (pinfunction "4_4") (pintype "passive"))
    )
    (net (code "184") (name "unconnected-(JP26-Pad5)") (class "Default")
      (node (ref "JP26") (pin "5") (pinfunction "5_5") (pintype "passive"))
    )
    (net (code "185") (name "unconnected-(JP26-Pad6)") (class "Default")
      (node (ref "JP26") (pin "6") (pinfunction "6_6") (pintype "passive"))
    )
    (net (code "186") (name "unconnected-(JP26-Pad7)") (class "Default")
      (node (ref "JP26") (pin "7") (pinfunction "7_7") (pintype "passive"))
    )
    (net (code "187") (name "unconnected-(JP26-Pad8)") (class "Default")
      (node (ref "JP26") (pin "8") (pinfunction "8_8") (pintype "passive"))
    )
    (net (code "188") (name "unconnected-(JP26-Pad9)") (class "Default")
      (node (ref "JP26") (pin "9") (pinfunction "9_9") (pintype "passive"))
    )
    (net (code "189") (name "unconnected-(JP26-Pad10)") (class "Default")
      (node (ref "JP26") (pin "10") (pinfunction "10_10") (pintype "passive"))
    )
    (net (code "190") (name "unconnected-(JP26-Pad11)") (class "Default")
      (node (ref "JP26") (pin "11") (pinfunction "11_11") (pintype "passive"))
    )
    (net (code "191") (name "unconnected-(JP27-Pad2)") (class "Default")
      (node (ref "JP27") (pin "2") (pinfunction "2_2") (pintype "passive"))
    )
    (net (code "192") (name "unconnected-(JP27-Pad3)") (class "Default")
      (node (ref "JP27") (pin "3") (pinfunction "3_3") (pintype "passive"))
    )
    (net (code "193") (name "unconnected-(JP27-Pad4)") (class "Default")
      (node (ref "JP27") (pin "4") (pinfunction "4_4") (pintype "passive"))
    )
    (net (code "194") (name "unconnected-(JP27-Pad5)") (class "Default")
      (node (ref "JP27") (pin "5") (pinfunction "5_5") (pintype "passive"))
    )
    (net (code "195") (name "unconnected-(JP27-Pad6)") (class "Default")
      (node (ref "JP27") (pin "6") (pinfunction "6_6") (pintype "passive"))
    )
    (net (code "196") (name "unconnected-(JP27-Pad7)") (class "Default")
      (node (ref "JP27") (pin "7") (pinfunction "7_7") (pintype "passive"))
    )
    (net (code "197") (name "unconnected-(JP27-Pad8)") (class "Default")
      (node (ref "JP27") (pin "8") (pinfunction "8_8") (pintype "passive"))
    )
    (net (code "198") (name "unconnected-(JP27-Pad9)") (class "Default")
      (node (ref "JP27") (pin "9") (pinfunction "9_9") (pintype "passive"))
    )
    (net (code "199") (name "unconnected-(JP27-Pad10)") (class "Default")
      (node (ref "JP27") (pin "10") (pinfunction "10_10") (pintype "passive"))
    )
    (net (code "200") (name "unconnected-(JP27-Pad11)") (class "Default")
      (node (ref "JP27") (pin "11") (pinfunction "11_11") (pintype "passive"))
    )
  )
)
